# DuoRS-485Shield.net
KiCad netlist of a schematic drawn in EAGLE
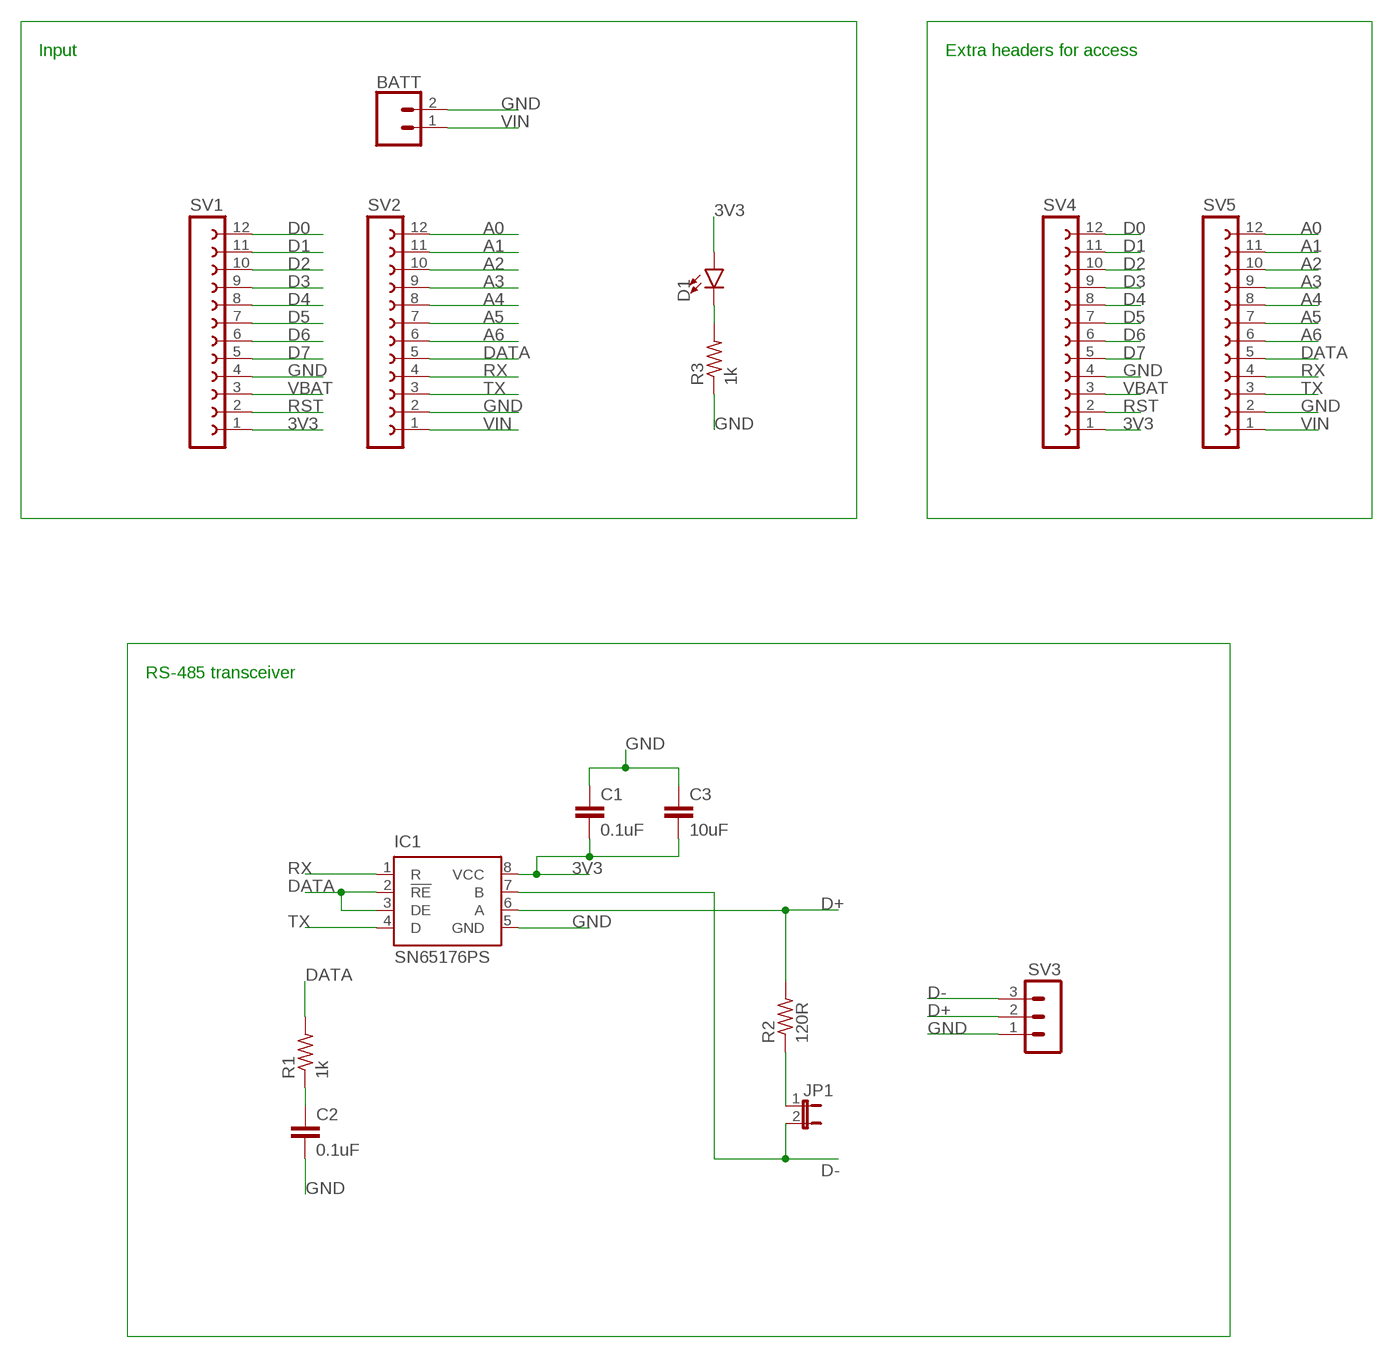
[diagram p0: schematic, sheet 1]

(export (version "E")
  (design (tool "Eeschema 10.0.6"))
  (components
    (comp (ref "BATT")
      (value "CONN_02JST-PTH-2")
      (footprint "eagle-import:JST-2-PTH")
      (libsource (lib "eagle-import") (part "CONN_02JST-PTH-2"))
    )
    (comp (ref "C1")
      (value "0.1uF")
      (footprint "eagle-import:0603")
      (libsource (lib "eagle-import") (part "0.1UF-0603-25V-5%"))
    )
    (comp (ref "C2")
      (value "0.1uF")
      (footprint "eagle-import:0603")
      (libsource (lib "eagle-import") (part "0.1UF-0603-25V-5%"))
    )
    (comp (ref "C3")
      (value "10uF")
      (footprint "eagle-import:0603")
      (libsource (lib "eagle-import") (part "10UF-0603-6.3V-20%"))
    )
    (comp (ref "D1")
      (value "LED-3MM-NO_SILK")
      (footprint "eagle-import:LED_3MM-NS")
      (libsource (lib "eagle-import") (part "LED-3MM-NO_SILK"))
    )
    (comp (ref "IC1")
      (value "SN65176PS")
      (footprint "eagle-import:SOP-08")
      (libsource (lib "eagle-import") (part "SN65176PS"))
    )
    (comp (ref "JP1")
      (value "JP1E")
      (footprint "eagle-import:JP1")
      (libsource (lib "eagle-import") (part "JP1E"))
    )
    (comp (ref "R1")
      (value "1k")
      (footprint "eagle-import:R0805")
      (libsource (lib "eagle-import") (part "R-US_R0805"))
    )
    (comp (ref "R2")
      (value "120R")
      (footprint "eagle-import:R0805")
      (libsource (lib "eagle-import") (part "R-US_R0805"))
    )
    (comp (ref "R3")
      (value "1k")
      (footprint "eagle-import:R0805")
      (libsource (lib "eagle-import") (part "R-US_R0805"))
    )
    (comp (ref "SV1")
      (value "FE12-1")
      (footprint "eagle-import:FE12")
      (libsource (lib "eagle-import") (part "FE12-1"))
    )
    (comp (ref "SV2")
      (value "FE12-1")
      (footprint "eagle-import:FE12")
      (libsource (lib "eagle-import") (part "FE12-1"))
    )
    (comp (ref "SV3")
      (value "MA03-1")
      (footprint "eagle-import:MA03-1")
      (libsource (lib "eagle-import") (part "MA03-1"))
    )
    (comp (ref "SV4")
      (value "FE12-1")
      (footprint "eagle-import:FE12")
      (libsource (lib "eagle-import") (part "FE12-1"))
    )
    (comp (ref "SV5")
      (value "FE12-1")
      (footprint "eagle-import:FE12")
      (libsource (lib "eagle-import") (part "FE12-1"))
    )
  )
  (nets
    (net (code "1") (name "/3V3") (class "Default")
      (node (ref "C1") (pin "2") (pinfunction "2_2") (pintype "passive"))
      (node (ref "C3") (pin "2") (pinfunction "2_2") (pintype "passive"))
      (node (ref "D1") (pin "A") (pinfunction "A_A") (pintype "passive"))
      (node (ref "IC1") (pin "8") (pinfunction "VCC_8") (pintype "input"))
      (node (ref "SV1") (pin "1") (pinfunction "1_1") (pintype "passive"))
      (node (ref "SV4") (pin "1") (pinfunction "1_1") (pintype "passive"))
    )
    (net (code "2") (name "/A0") (class "Default")
      (node (ref "SV2") (pin "12") (pinfunction "12_12") (pintype "passive"))
      (node (ref "SV5") (pin "12") (pinfunction "12_12") (pintype "passive"))
    )
    (net (code "3") (name "/A1") (class "Default")
      (node (ref "SV2") (pin "11") (pinfunction "11_11") (pintype "passive"))
      (node (ref "SV5") (pin "11") (pinfunction "11_11") (pintype "passive"))
    )
    (net (code "4") (name "/A2") (class "Default")
      (node (ref "SV2") (pin "10") (pinfunction "10_10") (pintype "passive"))
      (node (ref "SV5") (pin "10") (pinfunction "10_10") (pintype "passive"))
    )
    (net (code "5") (name "/A3") (class "Default")
      (node (ref "SV2") (pin "9") (pinfunction "9_9") (pintype "passive"))
      (node (ref "SV5") (pin "9") (pinfunction "9_9") (pintype "passive"))
    )
    (net (code "6") (name "/A4") (class "Default")
      (node (ref "SV2") (pin "8") (pinfunction "8_8") (pintype "passive"))
      (node (ref "SV5") (pin "8") (pinfunction "8_8") (pintype "passive"))
    )
    (net (code "7") (name "/A5") (class "Default")
      (node (ref "SV2") (pin "7") (pinfunction "7_7") (pintype "passive"))
      (node (ref "SV5") (pin "7") (pinfunction "7_7") (pintype "passive"))
    )
    (net (code "8") (name "/A6") (class "Default")
      (node (ref "SV2") (pin "6") (pinfunction "6_6") (pintype "passive"))
      (node (ref "SV5") (pin "6") (pinfunction "6_6") (pintype "passive"))
    )
    (net (code "9") (name "/D+") (class "Default")
      (node (ref "IC1") (pin "6") (pinfunction "A_6") (pintype "input"))
      (node (ref "R2") (pin "2") (pinfunction "2_2") (pintype "passive"))
      (node (ref "SV3") (pin "2") (pinfunction "2_2") (pintype "passive"))
    )
    (net (code "10") (name "/D-") (class "Default")
      (node (ref "IC1") (pin "7") (pinfunction "B_7") (pintype "input"))
      (node (ref "JP1") (pin "2") (pinfunction "2_2") (pintype "passive"))
      (node (ref "SV3") (pin "3") (pinfunction "3_3") (pintype "passive"))
    )
    (net (code "11") (name "/D0") (class "Default")
      (node (ref "SV1") (pin "12") (pinfunction "12_12") (pintype "passive"))
      (node (ref "SV4") (pin "12") (pinfunction "12_12") (pintype "passive"))
    )
    (net (code "12") (name "/D1") (class "Default")
      (node (ref "SV1") (pin "11") (pinfunction "11_11") (pintype "passive"))
      (node (ref "SV4") (pin "11") (pinfunction "11_11") (pintype "passive"))
    )
    (net (code "13") (name "/D2") (class "Default")
      (node (ref "SV1") (pin "10") (pinfunction "10_10") (pintype "passive"))
      (node (ref "SV4") (pin "10") (pinfunction "10_10") (pintype "passive"))
    )
    (net (code "14") (name "/D3") (class "Default")
      (node (ref "SV1") (pin "9") (pinfunction "9_9") (pintype "passive"))
      (node (ref "SV4") (pin "9") (pinfunction "9_9") (pintype "passive"))
    )
    (net (code "15") (name "/D4") (class "Default")
      (node (ref "SV1") (pin "8") (pinfunction "8_8") (pintype "passive"))
      (node (ref "SV4") (pin "8") (pinfunction "8_8") (pintype "passive"))
    )
    (net (code "16") (name "/D5") (class "Default")
      (node (ref "SV1") (pin "7") (pinfunction "7_7") (pintype "passive"))
      (node (ref "SV4") (pin "7") (pinfunction "7_7") (pintype "passive"))
    )
    (net (code "17") (name "/D6") (class "Default")
      (node (ref "SV1") (pin "6") (pinfunction "6_6") (pintype "passive"))
      (node (ref "SV4") (pin "6") (pinfunction "6_6") (pintype "passive"))
    )
    (net (code "18") (name "/D7") (class "Default")
      (node (ref "SV1") (pin "5") (pinfunction "5_5") (pintype "passive"))
      (node (ref "SV4") (pin "5") (pinfunction "5_5") (pintype "passive"))
    )
    (net (code "19") (name "/DATA") (class "Default")
      (node (ref "IC1") (pin "2") (pinfunction "~{RE}_2") (pintype "input"))
      (node (ref "IC1") (pin "3") (pinfunction "DE_3") (pintype "input"))
      (node (ref "R1") (pin "2") (pinfunction "2_2") (pintype "passive"))
      (node (ref "SV2") (pin "5") (pinfunction "5_5") (pintype "passive"))
      (node (ref "SV5") (pin "5") (pinfunction "5_5") (pintype "passive"))
    )
    (net (code "20") (name "/GND") (class "Default")
      (node (ref "BATT") (pin "2") (pinfunction "2_2") (pintype "passive"))
      (node (ref "C1") (pin "1") (pinfunction "1_1") (pintype "passive"))
      (node (ref "C2") (pin "2") (pinfunction "2_2") (pintype "passive"))
      (node (ref "C3") (pin "1") (pinfunction "1_1") (pintype "passive"))
      (node (ref "IC1") (pin "5") (pinfunction "GND_5") (pintype "input"))
      (node (ref "R3") (pin "1") (pinfunction "1_1") (pintype "passive"))
      (node (ref "SV1") (pin "4") (pinfunction "4_4") (pintype "passive"))
      (node (ref "SV2") (pin "2") (pinfunction "2_2") (pintype "passive"))
      (node (ref "SV3") (pin "1") (pinfunction "1_1") (pintype "passive"))
      (node (ref "SV4") (pin "4") (pinfunction "4_4") (pintype "passive"))
      (node (ref "SV5") (pin "2") (pinfunction "2_2") (pintype "passive"))
    )
    (net (code "21") (name "/RST") (class "Default")
      (node (ref "SV1") (pin "2") (pinfunction "2_2") (pintype "passive"))
      (node (ref "SV4") (pin "2") (pinfunction "2_2") (pintype "passive"))
    )
    (net (code "22") (name "/RX") (class "Default")
      (node (ref "IC1") (pin "1") (pinfunction "R_1") (pintype "input"))
      (node (ref "SV2") (pin "4") (pinfunction "4_4") (pintype "passive"))
      (node (ref "SV5") (pin "4") (pinfunction "4_4") (pintype "passive"))
    )
    (net (code "23") (name "/TX") (class "Default")
      (node (ref "IC1") (pin "4") (pinfunction "D_4") (pintype "input"))
      (node (ref "SV2") (pin "3") (pinfunction "3_3") (pintype "passive"))
      (node (ref "SV5") (pin "3") (pinfunction "3_3") (pintype "passive"))
    )
    (net (code "24") (name "/VBAT") (class "Default")
      (node (ref "SV1") (pin "3") (pinfunction "3_3") (pintype "passive"))
      (node (ref "SV4") (pin "3") (pinfunction "3_3") (pintype "passive"))
    )
    (net (code "25") (name "/VIN") (class "Default")
      (node (ref "BATT") (pin "1") (pinfunction "1_1") (pintype "passive"))
      (node (ref "SV2") (pin "1") (pinfunction "1_1") (pintype "passive"))
      (node (ref "SV5") (pin "1") (pinfunction "1_1") (pintype "passive"))
    )
    (net (code "26") (name "Net-(C2-Pad1)") (class "Default")
      (node (ref "C2") (pin "1") (pinfunction "1_1") (pintype "passive"))
      (node (ref "R1") (pin "1") (pinfunction "1_1") (pintype "passive"))
    )
    (net (code "27") (name "Net-(D1-C)") (class "Default")
      (node (ref "D1") (pin "K") (pinfunction "C_K") (pintype "passive"))
      (node (ref "R3") (pin "2") (pinfunction "2_2") (pintype "passive"))
    )
    (net (code "28") (name "Net-(JP1-Pad1)") (class "Default")
      (node (ref "JP1") (pin "1") (pinfunction "1_1") (pintype "passive"))
      (node (ref "R2") (pin "1") (pinfunction "1_1") (pintype "passive"))
    )
  )
)
